# MPR121_ATMega32u4.net
KiCad netlist of a schematic drawn in EAGLE
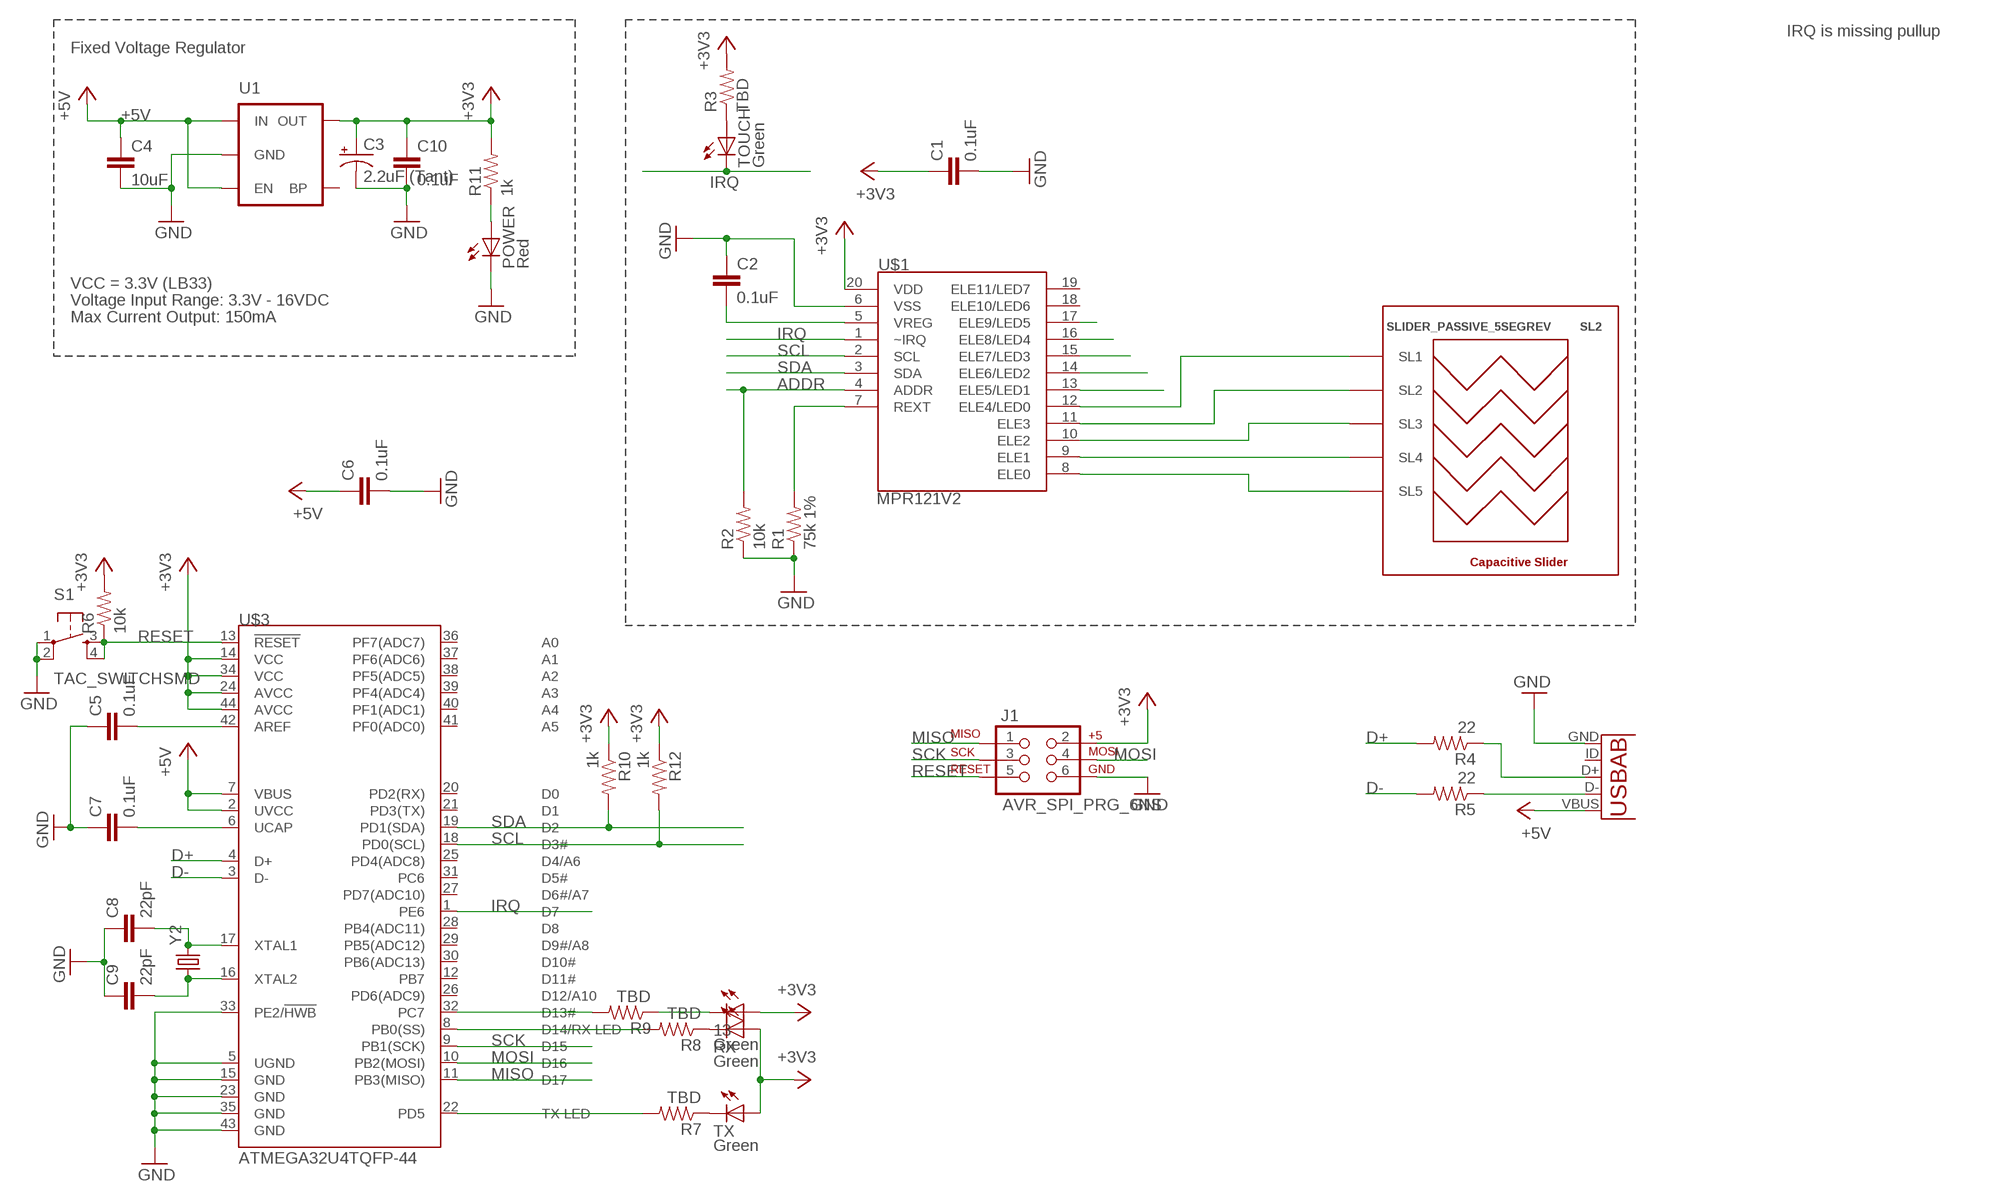
[diagram p0: schematic, sheet 1]

(export (version "E")
  (design (tool "Eeschema 10.0.6"))
  (components
    (comp (ref "13")
      (value "Green")
      (footprint "eagle-import:LED-1206")
      (libsource (lib "eagle-import") (part "LED-RED1206"))
    )
    (comp (ref "C1")
      (value "0.1uF")
      (footprint "eagle-import:0805")
      (libsource (lib "eagle-import") (part "CAP0805"))
    )
    (comp (ref "C2")
      (value "0.1uF")
      (footprint "eagle-import:0805")
      (libsource (lib "eagle-import") (part "CAP0805"))
    )
    (comp (ref "C3")
      (value "2.2uF (Tant)")
      (footprint "eagle-import:EIA3216")
      (libsource (lib "eagle-import") (part "CAP_POL1206"))
    )
    (comp (ref "C4")
      (value "10uF")
      (footprint "eagle-import:1206")
      (libsource (lib "eagle-import") (part "CAP1206"))
    )
    (comp (ref "C5")
      (value "0.1uF")
      (footprint "eagle-import:0805")
      (libsource (lib "eagle-import") (part "CAP0805"))
    )
    (comp (ref "C6")
      (value "0.1uF")
      (footprint "eagle-import:0805")
      (libsource (lib "eagle-import") (part "CAP0805"))
    )
    (comp (ref "C7")
      (value "0.1uF")
      (footprint "eagle-import:0805")
      (libsource (lib "eagle-import") (part "CAP0805"))
    )
    (comp (ref "C8")
      (value "22pF")
      (footprint "eagle-import:0805")
      (libsource (lib "eagle-import") (part "CAP0805"))
    )
    (comp (ref "C9")
      (value "22pF")
      (footprint "eagle-import:0805")
      (libsource (lib "eagle-import") (part "CAP0805"))
    )
    (comp (ref "C10")
      (value "0.1uF")
      (footprint "eagle-import:0805")
      (libsource (lib "eagle-import") (part "CAP0805"))
    )
    (comp (ref "J1")
      (value "AVR_SPI_PRG_6NS")
      (footprint "eagle-import:2X3-NS")
      (libsource (lib "eagle-import") (part "AVR_SPI_PRG_6NS"))
    )
    (comp (ref "POWER")
      (value "Red")
      (footprint "eagle-import:LED-1206")
      (libsource (lib "eagle-import") (part "LED-RED1206"))
    )
    (comp (ref "R1")
      (value "75k 1%")
      (footprint "eagle-import:0805")
      (libsource (lib "eagle-import") (part "RESISTOR0805-RES"))
    )
    (comp (ref "R2")
      (value "10k")
      (footprint "eagle-import:0805")
      (libsource (lib "eagle-import") (part "RESISTOR0805-RES"))
    )
    (comp (ref "R3")
      (value "TBD")
      (footprint "eagle-import:0805")
      (libsource (lib "eagle-import") (part "RESISTOR0805-RES"))
    )
    (comp (ref "R4")
      (value "22")
      (footprint "eagle-import:0805")
      (libsource (lib "eagle-import") (part "SparkFun-Resistors_RESISTOR0805-RES"))
    )
    (comp (ref "R5")
      (value "22")
      (footprint "eagle-import:0805")
      (libsource (lib "eagle-import") (part "SparkFun-Resistors_RESISTOR0805-RES"))
    )
    (comp (ref "R6")
      (value "10k")
      (footprint "eagle-import:0805")
      (libsource (lib "eagle-import") (part "SparkFun-Resistors_RESISTOR0805-RES"))
    )
    (comp (ref "R7")
      (value "TBD")
      (footprint "eagle-import:0805")
      (libsource (lib "eagle-import") (part "RESISTOR0805-RES"))
    )
    (comp (ref "R8")
      (value "TBD")
      (footprint "eagle-import:0805")
      (libsource (lib "eagle-import") (part "RESISTOR0805-RES"))
    )
    (comp (ref "R9")
      (value "TBD")
      (footprint "eagle-import:0805")
      (libsource (lib "eagle-import") (part "RESISTOR0805-RES"))
    )
    (comp (ref "R10")
      (value "1k")
      (footprint "eagle-import:0805")
      (libsource (lib "eagle-import") (part "RESISTOR0805-RES"))
    )
    (comp (ref "R11")
      (value "1k")
      (footprint "eagle-import:0805")
      (libsource (lib "eagle-import") (part "SparkFun-Resistors_RESISTOR0805-RES"))
    )
    (comp (ref "R12")
      (value "1k")
      (footprint "eagle-import:0805")
      (libsource (lib "eagle-import") (part "RESISTOR0805-RES"))
    )
    (comp (ref "RX")
      (value "Green")
      (footprint "eagle-import:LED-1206")
      (libsource (lib "eagle-import") (part "LED-RED1206"))
    )
    (comp (ref "S1")
      (value "TAC_SWITCHSMD")
      (footprint "eagle-import:TACTILE-SWITCH-SMD")
      (libsource (lib "eagle-import") (part "TAC_SWITCHSMD"))
    )
    (comp (ref "SL2")
      (value "SLIDER_PASSIVE_5SEGREV")
      (footprint "eagle-import:SLIDER_PASSIVE_5SEG_12MM_REV")
      (libsource (lib "eagle-import") (part "SLIDER_PASSIVE_5SEGREV"))
    )
    (comp (ref "TOUCH")
      (value "Green")
      (footprint "eagle-import:LED-1206")
      (libsource (lib "eagle-import") (part "LED-RED1206"))
    )
    (comp (ref "TX")
      (value "Green")
      (footprint "eagle-import:LED-1206")
      (libsource (lib "eagle-import") (part "LED-RED1206"))
    )
    (comp (ref "U$1")
      (value "MPR121V2")
      (footprint "eagle-import:QFN-20-0.4MM-V2")
      (libsource (lib "eagle-import") (part "MPR121V2"))
    )
    (comp (ref "U$3")
      (value "ATMEGA32U4TQFP-44")
      (footprint "eagle-import:TQFP44")
      (libsource (lib "eagle-import") (part "ATMEGA32U4TQFP-44"))
    )
    (comp (ref "U1")
      (value "MIC52053.3V")
      (footprint "eagle-import:SOT23-5")
      (libsource (lib "eagle-import") (part "MIC52053.3V"))
    )
    (comp (ref "U2")
      (value "USB-AB")
      (footprint "eagle-import:USB-AB-MICRO-SMD")
      (libsource (lib "eagle-import") (part "USB-AB"))
    )
    (comp (ref "Y2")
      (value "CRYSTAL5X3")
      (footprint "eagle-import:CRYSTAL-SMD-5X3")
      (libsource (lib "eagle-import") (part "CRYSTAL5X3"))
    )
  )
  (nets
    (net (code "1") (name "+3V3") (class "Default")
      (node (ref "13") (pin "A") (pinfunction "A_A") (pintype "passive"))
      (node (ref "C1") (pin "1") (pinfunction "1_1") (pintype "passive"))
      (node (ref "C10") (pin "1") (pinfunction "1_1") (pintype "passive"))
      (node (ref "C3") (pin "A") (pinfunction "+_A") (pintype "passive"))
      (node (ref "J1") (pin "2") (pinfunction "2_2") (pintype "passive"))
      (node (ref "R10") (pin "1") (pinfunction "1_1") (pintype "passive"))
      (node (ref "R11") (pin "2") (pinfunction "2_2") (pintype "passive"))
      (node (ref "R12") (pin "1") (pinfunction "1_1") (pintype "passive"))
      (node (ref "R3") (pin "2") (pinfunction "2_2") (pintype "passive"))
      (node (ref "R6") (pin "2") (pinfunction "2_2") (pintype "passive"))
      (node (ref "RX") (pin "A") (pinfunction "A_A") (pintype "passive"))
      (node (ref "TX") (pin "A") (pinfunction "A_A") (pintype "passive"))
      (node (ref "U$1") (pin "20") (pinfunction "VDD_20") (pintype "bidirectional"))
      (node (ref "U$3") (pin "14") (pinfunction "VCC_14") (pintype "bidirectional"))
      (node (ref "U$3") (pin "24") (pinfunction "AVCC_24") (pintype "bidirectional"))
      (node (ref "U$3") (pin "34") (pinfunction "VCC_34") (pintype "bidirectional"))
      (node (ref "U$3") (pin "44") (pinfunction "AVCC_44") (pintype "bidirectional"))
      (node (ref "U1") (pin "5") (pinfunction "OUT_5") (pintype "passive"))
    )
    (net (code "2") (name "+5V") (class "Default")
      (node (ref "C4") (pin "1") (pinfunction "1_1") (pintype "passive"))
      (node (ref "C6") (pin "1") (pinfunction "1_1") (pintype "passive"))
      (node (ref "U$3") (pin "2") (pinfunction "UVCC_2") (pintype "bidirectional"))
      (node (ref "U$3") (pin "7") (pinfunction "VBUS_7") (pintype "bidirectional"))
      (node (ref "U1") (pin "1") (pinfunction "IN_1") (pintype "input"))
      (node (ref "U1") (pin "3") (pinfunction "EN_3") (pintype "input"))
      (node (ref "U2") (pin "VBUS") (pinfunction "VBUS_VBUS") (pintype "bidirectional"))
    )
    (net (code "3") (name "/ADDR") (class "Default")
      (node (ref "R2") (pin "2") (pinfunction "2_2") (pintype "passive"))
      (node (ref "U$1") (pin "4") (pinfunction "ADDR_4") (pintype "bidirectional"))
    )
    (net (code "4") (name "/D+") (class "Default")
      (node (ref "R4") (pin "2") (pinfunction "2_2") (pintype "passive"))
      (node (ref "U$3") (pin "4") (pinfunction "D+_4") (pintype "bidirectional"))
    )
    (net (code "5") (name "/D-") (class "Default")
      (node (ref "R5") (pin "2") (pinfunction "2_2") (pintype "passive"))
      (node (ref "U$3") (pin "3") (pinfunction "D-_3") (pintype "bidirectional"))
    )
    (net (code "6") (name "/IRQ") (class "Default")
      (node (ref "TOUCH") (pin "C") (pinfunction "C_C") (pintype "passive"))
      (node (ref "U$1") (pin "1") (pinfunction "~{IRQ}_1") (pintype "bidirectional"))
      (node (ref "U$3") (pin "1") (pinfunction "PE6_1") (pintype "bidirectional"))
    )
    (net (code "7") (name "/MISO") (class "Default")
      (node (ref "J1") (pin "1") (pinfunction "1_1") (pintype "passive"))
      (node (ref "U$3") (pin "11") (pinfunction "PB3(MISO)_11") (pintype "bidirectional"))
    )
    (net (code "8") (name "/MOSI") (class "Default")
      (node (ref "J1") (pin "4") (pinfunction "4_4") (pintype "passive"))
      (node (ref "U$3") (pin "10") (pinfunction "PB2(MOSI)_10") (pintype "bidirectional"))
    )
    (net (code "9") (name "/RESET") (class "Default")
      (node (ref "J1") (pin "5") (pinfunction "5_5") (pintype "passive"))
      (node (ref "R6") (pin "1") (pinfunction "1_1") (pintype "passive"))
      (node (ref "S1") (pin "3") (pinfunction "3_3") (pintype "passive"))
      (node (ref "S1") (pin "4") (pinfunction "4_4") (pintype "passive"))
      (node (ref "U$3") (pin "13") (pinfunction "~{RESET}_13") (pintype "bidirectional"))
    )
    (net (code "10") (name "/SCK") (class "Default")
      (node (ref "J1") (pin "3") (pinfunction "3_3") (pintype "passive"))
      (node (ref "U$3") (pin "9") (pinfunction "PB1(SCK)_9") (pintype "bidirectional"))
    )
    (net (code "11") (name "/SCL") (class "Default")
      (node (ref "R12") (pin "2") (pinfunction "2_2") (pintype "passive"))
      (node (ref "U$1") (pin "2") (pinfunction "SCL_2") (pintype "bidirectional"))
      (node (ref "U$3") (pin "18") (pinfunction "PD0(SCL)_18") (pintype "bidirectional"))
    )
    (net (code "12") (name "/SDA") (class "Default")
      (node (ref "R10") (pin "2") (pinfunction "2_2") (pintype "passive"))
      (node (ref "U$1") (pin "3") (pinfunction "SDA_3") (pintype "bidirectional"))
      (node (ref "U$3") (pin "19") (pinfunction "PD1(SDA)_19") (pintype "bidirectional"))
    )
    (net (code "13") (name "GND") (class "Default")
      (node (ref "C1") (pin "2") (pinfunction "2_2") (pintype "passive"))
      (node (ref "C10") (pin "2") (pinfunction "2_2") (pintype "passive"))
      (node (ref "C2") (pin "1") (pinfunction "1_1") (pintype "passive"))
      (node (ref "C3") (pin "C") (pinfunction "-_C") (pintype "passive"))
      (node (ref "C4") (pin "2") (pinfunction "2_2") (pintype "passive"))
      (node (ref "C5") (pin "1") (pinfunction "1_1") (pintype "passive"))
      (node (ref "C6") (pin "2") (pinfunction "2_2") (pintype "passive"))
      (node (ref "C7") (pin "1") (pinfunction "1_1") (pintype "passive"))
      (node (ref "C8") (pin "1") (pinfunction "1_1") (pintype "passive"))
      (node (ref "C9") (pin "1") (pinfunction "1_1") (pintype "passive"))
      (node (ref "J1") (pin "6") (pinfunction "6_6") (pintype "passive"))
      (node (ref "POWER") (pin "C") (pinfunction "C_C") (pintype "passive"))
      (node (ref "R1") (pin "1") (pinfunction "1_1") (pintype "passive"))
      (node (ref "R2") (pin "1") (pinfunction "1_1") (pintype "passive"))
      (node (ref "S1") (pin "1") (pinfunction "1_1") (pintype "passive"))
      (node (ref "S1") (pin "2") (pinfunction "2_2") (pintype "passive"))
      (node (ref "U$1") (pin "6") (pinfunction "VSS_6") (pintype "bidirectional"))
      (node (ref "U$3") (pin "15") (pinfunction "GND_15") (pintype "bidirectional"))
      (node (ref "U$3") (pin "23") (pinfunction "GND_23") (pintype "bidirectional"))
      (node (ref "U$3") (pin "33") (pinfunction "PE2/~{HWB}_33") (pintype "bidirectional"))
      (node (ref "U$3") (pin "35") (pinfunction "GND_35") (pintype "bidirectional"))
      (node (ref "U$3") (pin "43") (pinfunction "GND_43") (pintype "bidirectional"))
      (node (ref "U$3") (pin "5") (pinfunction "UGND_5") (pintype "bidirectional"))
      (node (ref "U1") (pin "2") (pinfunction "GND_2") (pintype "input"))
      (node (ref "U2") (pin "GND") (pinfunction "GND_GND") (pintype "bidirectional"))
    )
    (net (code "14") (name "Net-(13-PadC)") (class "Default")
      (node (ref "13") (pin "C") (pinfunction "C_C") (pintype "passive"))
      (node (ref "R9") (pin "1") (pinfunction "1_1") (pintype "passive"))
    )
    (net (code "15") (name "Net-(POWER-PadA)") (class "Default")
      (node (ref "POWER") (pin "A") (pinfunction "A_A") (pintype "passive"))
      (node (ref "R11") (pin "1") (pinfunction "1_1") (pintype "passive"))
    )
    (net (code "16") (name "Net-(R3-Pad1)") (class "Default")
      (node (ref "R3") (pin "1") (pinfunction "1_1") (pintype "passive"))
      (node (ref "TOUCH") (pin "A") (pinfunction "A_A") (pintype "passive"))
    )
    (net (code "17") (name "Net-(R4-Pad1)") (class "Default")
      (node (ref "R4") (pin "1") (pinfunction "1_1") (pintype "passive"))
      (node (ref "U2") (pin "D+") (pinfunction "D+_D+") (pintype "bidirectional"))
    )
    (net (code "18") (name "Net-(R5-Pad1)") (class "Default")
      (node (ref "R5") (pin "1") (pinfunction "1_1") (pintype "passive"))
      (node (ref "U2") (pin "D-") (pinfunction "D-_D-") (pintype "bidirectional"))
    )
    (net (code "19") (name "Net-(R7-Pad1)") (class "Default")
      (node (ref "R7") (pin "1") (pinfunction "1_1") (pintype "passive"))
      (node (ref "TX") (pin "C") (pinfunction "C_C") (pintype "passive"))
    )
    (net (code "20") (name "Net-(R8-Pad1)") (class "Default")
      (node (ref "R8") (pin "1") (pinfunction "1_1") (pintype "passive"))
      (node (ref "RX") (pin "C") (pinfunction "C_C") (pintype "passive"))
    )
    (net (code "21") (name "Net-(U$1-ELE0)") (class "Default")
      (node (ref "SL2") (pin "SL5") (pinfunction "SL5_SL5") (pintype "passive"))
      (node (ref "U$1") (pin "8") (pinfunction "ELE0_8") (pintype "bidirectional"))
    )
    (net (code "22") (name "Net-(U$1-ELE1)") (class "Default")
      (node (ref "SL2") (pin "SL4") (pinfunction "SL4_SL4") (pintype "passive"))
      (node (ref "U$1") (pin "9") (pinfunction "ELE1_9") (pintype "bidirectional"))
    )
    (net (code "23") (name "Net-(U$1-ELE2)") (class "Default")
      (node (ref "SL2") (pin "SL3") (pinfunction "SL3_SL3") (pintype "passive"))
      (node (ref "U$1") (pin "10") (pinfunction "ELE2_10") (pintype "bidirectional"))
    )
    (net (code "24") (name "Net-(U$1-ELE3)") (class "Default")
      (node (ref "SL2") (pin "SL2") (pinfunction "SL2_SL2") (pintype "passive"))
      (node (ref "U$1") (pin "11") (pinfunction "ELE3_11") (pintype "bidirectional"))
    )
    (net (code "25") (name "Net-(U$1-ELE4{slash}LED0)") (class "Default")
      (node (ref "SL2") (pin "SL1") (pinfunction "SL1_SL1") (pintype "passive"))
      (node (ref "U$1") (pin "12") (pinfunction "ELE4/LED0_12") (pintype "bidirectional"))
    )
    (net (code "26") (name "Net-(U$1-REXT)") (class "Default")
      (node (ref "R1") (pin "2") (pinfunction "2_2") (pintype "passive"))
      (node (ref "U$1") (pin "7") (pinfunction "REXT_7") (pintype "bidirectional"))
    )
    (net (code "27") (name "Net-(U$1-VREG)") (class "Default")
      (node (ref "C2") (pin "2") (pinfunction "2_2") (pintype "passive"))
      (node (ref "U$1") (pin "5") (pinfunction "VREG_5") (pintype "bidirectional"))
    )
    (net (code "28") (name "Net-(U$3-AREF)") (class "Default")
      (node (ref "C5") (pin "2") (pinfunction "2_2") (pintype "passive"))
      (node (ref "U$3") (pin "42") (pinfunction "AREF_42") (pintype "bidirectional"))
    )
    (net (code "29") (name "Net-(U$3-PB0(SS))") (class "Default")
      (node (ref "R8") (pin "2") (pinfunction "2_2") (pintype "passive"))
      (node (ref "U$3") (pin "8") (pinfunction "PB0(SS)_8") (pintype "bidirectional"))
    )
    (net (code "30") (name "Net-(U$3-PC7)") (class "Default")
      (node (ref "R9") (pin "2") (pinfunction "2_2") (pintype "passive"))
      (node (ref "U$3") (pin "32") (pinfunction "PC7_32") (pintype "bidirectional"))
    )
    (net (code "31") (name "Net-(U$3-PD5)") (class "Default")
      (node (ref "R7") (pin "2") (pinfunction "2_2") (pintype "passive"))
      (node (ref "U$3") (pin "22") (pinfunction "PD5_22") (pintype "bidirectional"))
    )
    (net (code "32") (name "Net-(U$3-UCAP)") (class "Default")
      (node (ref "C7") (pin "2") (pinfunction "2_2") (pintype "passive"))
      (node (ref "U$3") (pin "6") (pinfunction "UCAP_6") (pintype "bidirectional"))
    )
    (net (code "33") (name "Net-(U$3-XTAL1)") (class "Default")
      (node (ref "C8") (pin "2") (pinfunction "2_2") (pintype "passive"))
      (node (ref "U$3") (pin "17") (pinfunction "XTAL1_17") (pintype "bidirectional"))
      (node (ref "Y2") (pin "3") (pinfunction "2_3") (pintype "passive"))
    )
    (net (code "34") (name "Net-(U$3-XTAL2)") (class "Default")
      (node (ref "C9") (pin "2") (pinfunction "2_2") (pintype "passive"))
      (node (ref "U$3") (pin "16") (pinfunction "XTAL2_16") (pintype "bidirectional"))
      (node (ref "Y2") (pin "1") (pinfunction "1_1") (pintype "passive"))
    )
    (net (code "35") (name "unconnected-(U$1-ELE5{slash}LED1-Pad13)") (class "Default")
      (node (ref "U$1") (pin "13") (pinfunction "ELE5/LED1_13") (pintype "bidirectional"))
    )
    (net (code "36") (name "unconnected-(U$1-ELE6{slash}LED2-Pad14)") (class "Default")
      (node (ref "U$1") (pin "14") (pinfunction "ELE6/LED2_14") (pintype "bidirectional"))
    )
    (net (code "37") (name "unconnected-(U$1-ELE7{slash}LED3-Pad15)") (class "Default")
      (node (ref "U$1") (pin "15") (pinfunction "ELE7/LED3_15") (pintype "bidirectional"))
    )
    (net (code "38") (name "unconnected-(U$1-ELE8{slash}LED4-Pad16)") (class "Default")
      (node (ref "U$1") (pin "16") (pinfunction "ELE8/LED4_16") (pintype "bidirectional"))
    )
    (net (code "39") (name "unconnected-(U$1-ELE9{slash}LED5-Pad17)") (class "Default")
      (node (ref "U$1") (pin "17") (pinfunction "ELE9/LED5_17") (pintype "bidirectional"))
    )
    (net (code "40") (name "unconnected-(U$1-ELE10{slash}LED6-Pad18)") (class "Default")
      (node (ref "U$1") (pin "18") (pinfunction "ELE10/LED6_18") (pintype "bidirectional"))
    )
    (net (code "41") (name "unconnected-(U$1-ELE11{slash}LED7-Pad19)") (class "Default")
      (node (ref "U$1") (pin "19") (pinfunction "ELE11/LED7_19") (pintype "bidirectional"))
    )
    (net (code "42") (name "unconnected-(U$3-PB4(ADC11)-Pad28)") (class "Default")
      (node (ref "U$3") (pin "28") (pinfunction "PB4(ADC11)_28") (pintype "bidirectional"))
    )
    (net (code "43") (name "unconnected-(U$3-PB5(ADC12)-Pad29)") (class "Default")
      (node (ref "U$3") (pin "29") (pinfunction "PB5(ADC12)_29") (pintype "bidirectional"))
    )
    (net (code "44") (name "unconnected-(U$3-PB6(ADC13)-Pad30)") (class "Default")
      (node (ref "U$3") (pin "30") (pinfunction "PB6(ADC13)_30") (pintype "bidirectional"))
    )
    (net (code "45") (name "unconnected-(U$3-PB7-Pad12)") (class "Default")
      (node (ref "U$3") (pin "12") (pinfunction "PB7_12") (pintype "bidirectional"))
    )
    (net (code "46") (name "unconnected-(U$3-PC6-Pad31)") (class "Default")
      (node (ref "U$3") (pin "31") (pinfunction "PC6_31") (pintype "bidirectional"))
    )
    (net (code "47") (name "unconnected-(U$3-PD2(RX)-Pad20)") (class "Default")
      (node (ref "U$3") (pin "20") (pinfunction "PD2(RX)_20") (pintype "bidirectional"))
    )
    (net (code "48") (name "unconnected-(U$3-PD3(TX)-Pad21)") (class "Default")
      (node (ref "U$3") (pin "21") (pinfunction "PD3(TX)_21") (pintype "bidirectional"))
    )
    (net (code "49") (name "unconnected-(U$3-PD4(ADC8)-Pad25)") (class "Default")
      (node (ref "U$3") (pin "25") (pinfunction "PD4(ADC8)_25") (pintype "bidirectional"))
    )
    (net (code "50") (name "unconnected-(U$3-PD6(ADC9)-Pad26)") (class "Default")
      (node (ref "U$3") (pin "26") (pinfunction "PD6(ADC9)_26") (pintype "bidirectional"))
    )
    (net (code "51") (name "unconnected-(U$3-PD7(ADC10)-Pad27)") (class "Default")
      (node (ref "U$3") (pin "27") (pinfunction "PD7(ADC10)_27") (pintype "bidirectional"))
    )
    (net (code "52") (name "unconnected-(U$3-PF0(ADC0)-Pad41)") (class "Default")
      (node (ref "U$3") (pin "41") (pinfunction "PF0(ADC0)_41") (pintype "bidirectional"))
    )
    (net (code "53") (name "unconnected-(U$3-PF1(ADC1)-Pad40)") (class "Default")
      (node (ref "U$3") (pin "40") (pinfunction "PF1(ADC1)_40") (pintype "bidirectional"))
    )
    (net (code "54") (name "unconnected-(U$3-PF4(ADC4)-Pad39)") (class "Default")
      (node (ref "U$3") (pin "39") (pinfunction "PF4(ADC4)_39") (pintype "bidirectional"))
    )
    (net (code "55") (name "unconnected-(U$3-PF5(ADC5)-Pad38)") (class "Default")
      (node (ref "U$3") (pin "38") (pinfunction "PF5(ADC5)_38") (pintype "bidirectional"))
    )
    (net (code "56") (name "unconnected-(U$3-PF6(ADC6)-Pad37)") (class "Default")
      (node (ref "U$3") (pin "37") (pinfunction "PF6(ADC6)_37") (pintype "bidirectional"))
    )
    (net (code "57") (name "unconnected-(U$3-PF7(ADC7)-Pad36)") (class "Default")
      (node (ref "U$3") (pin "36") (pinfunction "PF7(ADC7)_36") (pintype "bidirectional"))
    )
    (net (code "58") (name "unconnected-(U1-BP-Pad4)") (class "Default")
      (node (ref "U1") (pin "4") (pinfunction "BP_4") (pintype "input"))
    )
    (net (code "59") (name "unconnected-(U2-USBID-PadID)") (class "Default")
      (node (ref "U2") (pin "ID") (pinfunction "USBID_ID") (pintype "bidirectional"))
    )
  )
)
